# Interface.net
KiCad netlist of a schematic drawn in Altium Designer
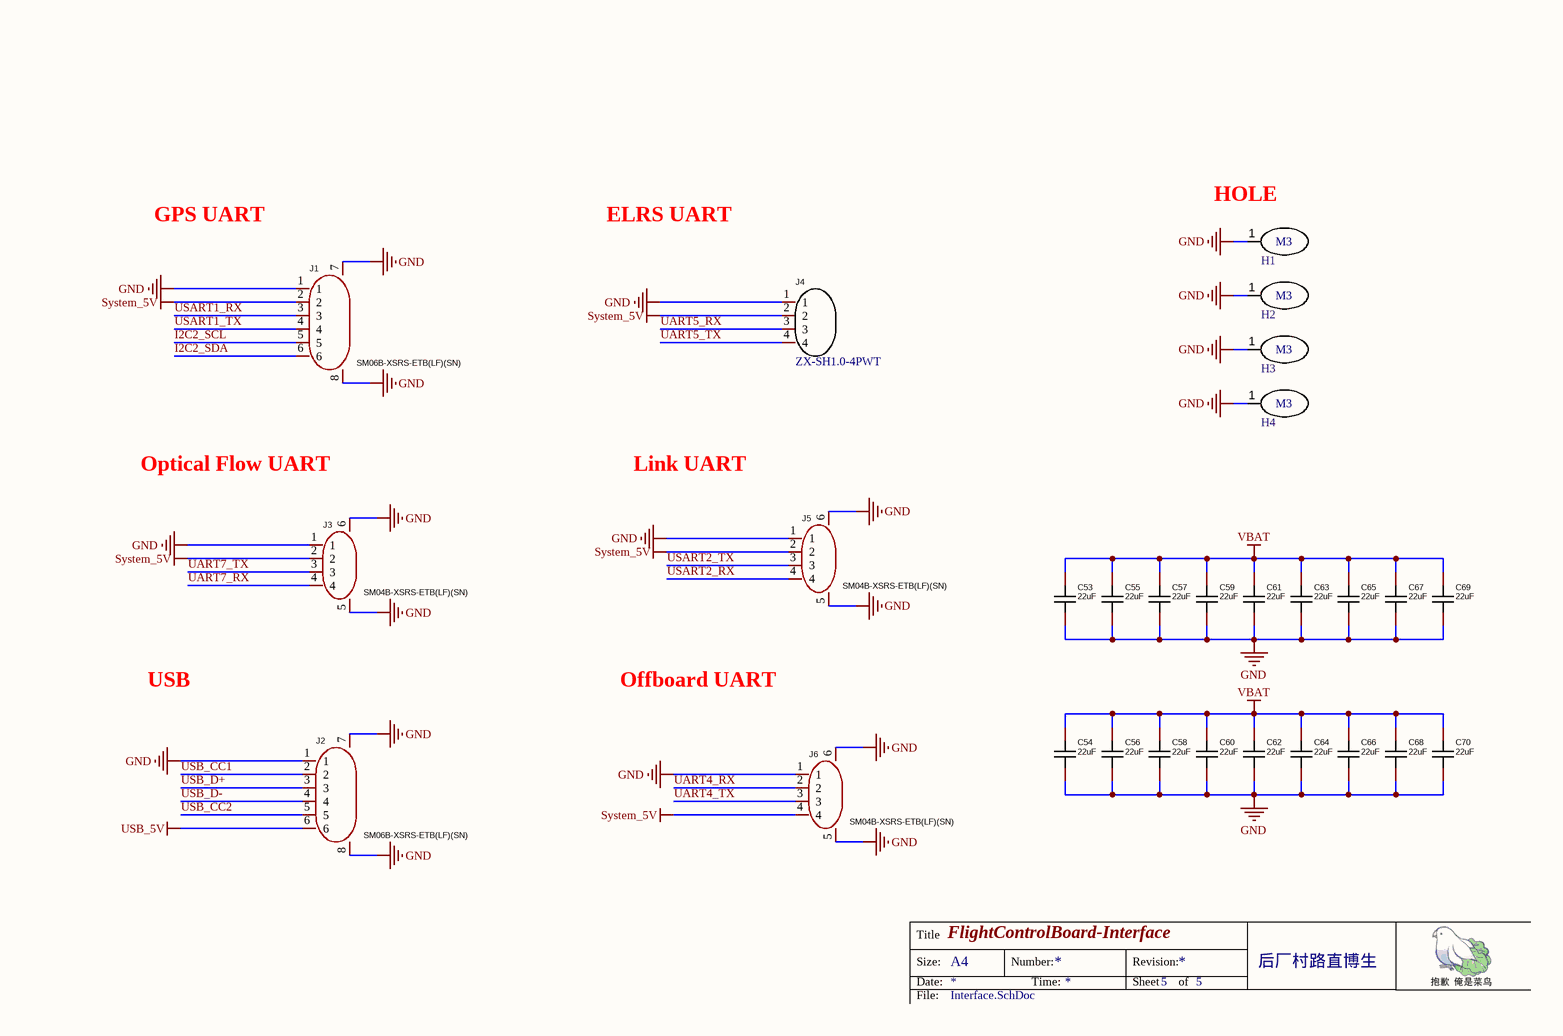
[diagram p0: Interface.SchDoc]

(export (version "E")
  (design (tool "Eeschema 10.0.6"))
  (components
    (comp (ref "C53")
      (value "22uF")
      (footprint "C0805")
      (libsource (lib "Capacitor") (part "CC0603KRX7R9BB104"))
    )
    (comp (ref "C54")
      (value "22uF")
      (footprint "C0805")
      (libsource (lib "Capacitor") (part "CC0603KRX7R9BB104"))
    )
    (comp (ref "C55")
      (value "22uF")
      (footprint "C0805")
      (libsource (lib "Capacitor") (part "CC0603KRX7R9BB104"))
    )
    (comp (ref "C56")
      (value "22uF")
      (footprint "C0805")
      (libsource (lib "Capacitor") (part "CC0603KRX7R9BB104"))
    )
    (comp (ref "C57")
      (value "22uF")
      (footprint "C0805")
      (libsource (lib "Capacitor") (part "CC0603KRX7R9BB104"))
    )
    (comp (ref "C58")
      (value "22uF")
      (footprint "C0805")
      (libsource (lib "Capacitor") (part "CC0603KRX7R9BB104"))
    )
    (comp (ref "C59")
      (value "22uF")
      (footprint "C0805")
      (libsource (lib "Capacitor") (part "CC0603KRX7R9BB104"))
    )
    (comp (ref "C60")
      (value "22uF")
      (footprint "C0805")
      (libsource (lib "Capacitor") (part "CC0603KRX7R9BB104"))
    )
    (comp (ref "C61")
      (value "22uF")
      (footprint "C0805")
      (libsource (lib "Capacitor") (part "CC0603KRX7R9BB104"))
    )
    (comp (ref "C62")
      (value "22uF")
      (footprint "C0805")
      (libsource (lib "Capacitor") (part "CC0603KRX7R9BB104"))
    )
    (comp (ref "C63")
      (value "22uF")
      (footprint "C0805")
      (libsource (lib "Capacitor") (part "CC0603KRX7R9BB104"))
    )
    (comp (ref "C64")
      (value "22uF")
      (footprint "C0805")
      (libsource (lib "Capacitor") (part "CC0603KRX7R9BB104"))
    )
    (comp (ref "C65")
      (value "22uF")
      (footprint "C0805")
      (libsource (lib "Capacitor") (part "CC0603KRX7R9BB104"))
    )
    (comp (ref "C66")
      (value "22uF")
      (footprint "C0805")
      (libsource (lib "Capacitor") (part "CC0603KRX7R9BB104"))
    )
    (comp (ref "C67")
      (value "22uF")
      (footprint "C0805")
      (libsource (lib "Capacitor") (part "CC0603KRX7R9BB104"))
    )
    (comp (ref "C68")
      (value "22uF")
      (footprint "C0805")
      (libsource (lib "Capacitor") (part "CC0603KRX7R9BB104"))
    )
    (comp (ref "C69")
      (value "22uF")
      (footprint "C0805")
      (libsource (lib "Capacitor") (part "CC0603KRX7R9BB104"))
    )
    (comp (ref "C70")
      (value "22uF")
      (footprint "C0805")
      (libsource (lib "Capacitor") (part "CC0603KRX7R9BB104"))
    )
    (comp (ref "H1") (value "M3_HOLE") (footprint "M3_HOLE") (libsource (lib "HOLE") (part "M3_HOLE")))
    (comp (ref "H2") (value "M3_HOLE") (footprint "M3_HOLE") (libsource (lib "HOLE") (part "M3_HOLE")))
    (comp (ref "H3") (value "M3_HOLE") (footprint "M3_HOLE") (libsource (lib "HOLE") (part "M3_HOLE")))
    (comp (ref "H4") (value "M3_HOLE") (footprint "M3_HOLE") (libsource (lib "HOLE") (part "M3_HOLE")))
    (comp (ref "J1")
      (value "SM06B-XSRS-ETB(LF)(SN)")
      (footprint "CONN-SMD_6P-P0.6")
      (fields (field (name "MANUFACTURER") "JST"))
      (libsource (lib "XSR0.6") (part "SM06B-XSRS-ETB(LF)(SN)"))
    )
    (comp (ref "J2")
      (value "SM06B-XSRS-ETB(LF)(SN)")
      (footprint "CONN-SMD_6P-P0.6")
      (fields (field (name "MANUFACTURER") "JST"))
      (libsource (lib "XSR0.6") (part "SM06B-XSRS-ETB(LF)(SN)"))
    )
    (comp (ref "J3")
      (value "SM04B-XSRS-ETB(LF)(SN)")
      (footprint "CONN-SMD_4P-P0.6")
      (fields (field (name "MANUFACTURER") "JST"))
      (libsource (lib "XSR0.6") (part "SM04B-XSRS-ETB(LF)(SN)"))
    )
    (comp (ref "J4") (value "ZX-SH1.0-4PWT") (footprint "ELRSPad") (libsource (lib "Pad") (part "ELRSPad")))
    (comp (ref "J5")
      (value "SM04B-XSRS-ETB(LF)(SN)")
      (footprint "CONN-SMD_4P-P0.6")
      (fields (field (name "MANUFACTURER") "JST"))
      (libsource (lib "XSR0.6") (part "SM04B-XSRS-ETB(LF)(SN)"))
    )
    (comp (ref "J6")
      (value "SM04B-XSRS-ETB(LF)(SN)")
      (footprint "CONN-SMD_4P-P0.6")
      (fields (field (name "MANUFACTURER") "JST"))
      (libsource (lib "XSR0.6") (part "SM04B-XSRS-ETB(LF)(SN)"))
    )
  )
  (nets
    (net (code "1") (name "/I2C2_SCL") (class "Default")
      (node (ref "J1") (pin "5") (pinfunction "5_5") (pintype "passive"))
    )
    (net (code "2") (name "/I2C2_SDA") (class "Default")
      (node (ref "J1") (pin "6") (pinfunction "6_6") (pintype "passive"))
    )
    (net (code "3") (name "/UART4_RX") (class "Default")
      (node (ref "J6") (pin "2") (pinfunction "2_2") (pintype "passive"))
    )
    (net (code "4") (name "/UART4_TX") (class "Default")
      (node (ref "J6") (pin "3") (pinfunction "3_3") (pintype "passive"))
    )
    (net (code "5") (name "/UART5_RX") (class "Default")
      (node (ref "J4") (pin "3") (pinfunction "3_3") (pintype "passive"))
    )
    (net (code "6") (name "/UART5_TX") (class "Default")
      (node (ref "J4") (pin "4") (pinfunction "4_4") (pintype "passive"))
    )
    (net (code "7") (name "/UART7_RX") (class "Default")
      (node (ref "J3") (pin "4") (pinfunction "4_4") (pintype "passive"))
    )
    (net (code "8") (name "/UART7_TX") (class "Default")
      (node (ref "J3") (pin "3") (pinfunction "3_3") (pintype "passive"))
    )
    (net (code "9") (name "/USART1_RX") (class "Default")
      (node (ref "J1") (pin "3") (pinfunction "3_3") (pintype "passive"))
    )
    (net (code "10") (name "/USART1_TX") (class "Default")
      (node (ref "J1") (pin "4") (pinfunction "4_4") (pintype "passive"))
    )
    (net (code "11") (name "/USART2_RX") (class "Default")
      (node (ref "J5") (pin "4") (pinfunction "4_4") (pintype "passive"))
    )
    (net (code "12") (name "/USART2_TX") (class "Default")
      (node (ref "J5") (pin "3") (pinfunction "3_3") (pintype "passive"))
    )
    (net (code "13") (name "/USB_CC1") (class "Default")
      (node (ref "J2") (pin "2") (pinfunction "2_2") (pintype "passive"))
    )
    (net (code "14") (name "/USB_CC2") (class "Default")
      (node (ref "J2") (pin "5") (pinfunction "5_5") (pintype "passive"))
    )
    (net (code "15") (name "/USB_D+") (class "Default")
      (node (ref "J2") (pin "3") (pinfunction "3_3") (pintype "passive"))
    )
    (net (code "16") (name "/USB_D-") (class "Default")
      (node (ref "J2") (pin "4") (pinfunction "4_4") (pintype "passive"))
    )
    (net (code "17") (name "GND") (class "Default")
      (node (ref "C53") (pin "2") (pinfunction "2_2") (pintype "passive"))
      (node (ref "C54") (pin "2") (pinfunction "2_2") (pintype "passive"))
      (node (ref "C55") (pin "2") (pinfunction "2_2") (pintype "passive"))
      (node (ref "C56") (pin "2") (pinfunction "2_2") (pintype "passive"))
      (node (ref "C57") (pin "2") (pinfunction "2_2") (pintype "passive"))
      (node (ref "C58") (pin "2") (pinfunction "2_2") (pintype "passive"))
      (node (ref "C59") (pin "2") (pinfunction "2_2") (pintype "passive"))
      (node (ref "C60") (pin "2") (pinfunction "2_2") (pintype "passive"))
      (node (ref "C61") (pin "2") (pinfunction "2_2") (pintype "passive"))
      (node (ref "C62") (pin "2") (pinfunction "2_2") (pintype "passive"))
      (node (ref "C63") (pin "2") (pinfunction "2_2") (pintype "passive"))
      (node (ref "C64") (pin "2") (pinfunction "2_2") (pintype "passive"))
      (node (ref "C65") (pin "2") (pinfunction "2_2") (pintype "passive"))
      (node (ref "C66") (pin "2") (pinfunction "2_2") (pintype "passive"))
      (node (ref "C67") (pin "2") (pinfunction "2_2") (pintype "passive"))
      (node (ref "C68") (pin "2") (pinfunction "2_2") (pintype "passive"))
      (node (ref "C69") (pin "2") (pinfunction "2_2") (pintype "passive"))
      (node (ref "C70") (pin "2") (pinfunction "2_2") (pintype "passive"))
      (node (ref "H1") (pin "1") (pinfunction "1_1") (pintype "passive"))
      (node (ref "H2") (pin "1") (pinfunction "1_1") (pintype "passive"))
      (node (ref "H3") (pin "1") (pinfunction "1_1") (pintype "passive"))
      (node (ref "H4") (pin "1") (pinfunction "1_1") (pintype "passive"))
      (node (ref "J1") (pin "1") (pinfunction "1_1") (pintype "passive"))
      (node (ref "J1") (pin "7") (pinfunction "7_7") (pintype "passive"))
      (node (ref "J1") (pin "8") (pinfunction "8_8") (pintype "passive"))
      (node (ref "J2") (pin "1") (pinfunction "1_1") (pintype "passive"))
      (node (ref "J2") (pin "7") (pinfunction "7_7") (pintype "passive"))
      (node (ref "J2") (pin "8") (pinfunction "8_8") (pintype "passive"))
      (node (ref "J3") (pin "1") (pinfunction "1_1") (pintype "passive"))
      (node (ref "J3") (pin "5") (pinfunction "5_5") (pintype "passive"))
      (node (ref "J3") (pin "6") (pinfunction "6_6") (pintype "passive"))
      (node (ref "J4") (pin "1") (pinfunction "1_1") (pintype "passive"))
      (node (ref "J5") (pin "1") (pinfunction "1_1") (pintype "passive"))
      (node (ref "J5") (pin "5") (pinfunction "5_5") (pintype "passive"))
      (node (ref "J5") (pin "6") (pinfunction "6_6") (pintype "passive"))
      (node (ref "J6") (pin "1") (pinfunction "1_1") (pintype "passive"))
      (node (ref "J6") (pin "5") (pinfunction "5_5") (pintype "passive"))
      (node (ref "J6") (pin "6") (pinfunction "6_6") (pintype "passive"))
    )
    (net (code "18") (name "System_5V") (class "Default")
      (node (ref "J1") (pin "2") (pinfunction "2_2") (pintype "passive"))
      (node (ref "J3") (pin "2") (pinfunction "2_2") (pintype "passive"))
      (node (ref "J4") (pin "2") (pinfunction "2_2") (pintype "passive"))
      (node (ref "J5") (pin "2") (pinfunction "2_2") (pintype "passive"))
      (node (ref "J6") (pin "4") (pinfunction "4_4") (pintype "passive"))
    )
    (net (code "19") (name "USB_5V") (class "Default")
      (node (ref "J2") (pin "6") (pinfunction "6_6") (pintype "passive"))
    )
    (net (code "20") (name "VBAT") (class "Default")
      (node (ref "C53") (pin "1") (pinfunction "1_1") (pintype "passive"))
      (node (ref "C54") (pin "1") (pinfunction "1_1") (pintype "passive"))
      (node (ref "C55") (pin "1") (pinfunction "1_1") (pintype "passive"))
      (node (ref "C56") (pin "1") (pinfunction "1_1") (pintype "passive"))
      (node (ref "C57") (pin "1") (pinfunction "1_1") (pintype "passive"))
      (node (ref "C58") (pin "1") (pinfunction "1_1") (pintype "passive"))
      (node (ref "C59") (pin "1") (pinfunction "1_1") (pintype "passive"))
      (node (ref "C60") (pin "1") (pinfunction "1_1") (pintype "passive"))
      (node (ref "C61") (pin "1") (pinfunction "1_1") (pintype "passive"))
      (node (ref "C62") (pin "1") (pinfunction "1_1") (pintype "passive"))
      (node (ref "C63") (pin "1") (pinfunction "1_1") (pintype "passive"))
      (node (ref "C64") (pin "1") (pinfunction "1_1") (pintype "passive"))
      (node (ref "C65") (pin "1") (pinfunction "1_1") (pintype "passive"))
      (node (ref "C66") (pin "1") (pinfunction "1_1") (pintype "passive"))
      (node (ref "C67") (pin "1") (pinfunction "1_1") (pintype "passive"))
      (node (ref "C68") (pin "1") (pinfunction "1_1") (pintype "passive"))
      (node (ref "C69") (pin "1") (pinfunction "1_1") (pintype "passive"))
      (node (ref "C70") (pin "1") (pinfunction "1_1") (pintype "passive"))
    )
  )
)
